# leds.net
KiCad netlist of a schematic drawn in Altium Designer
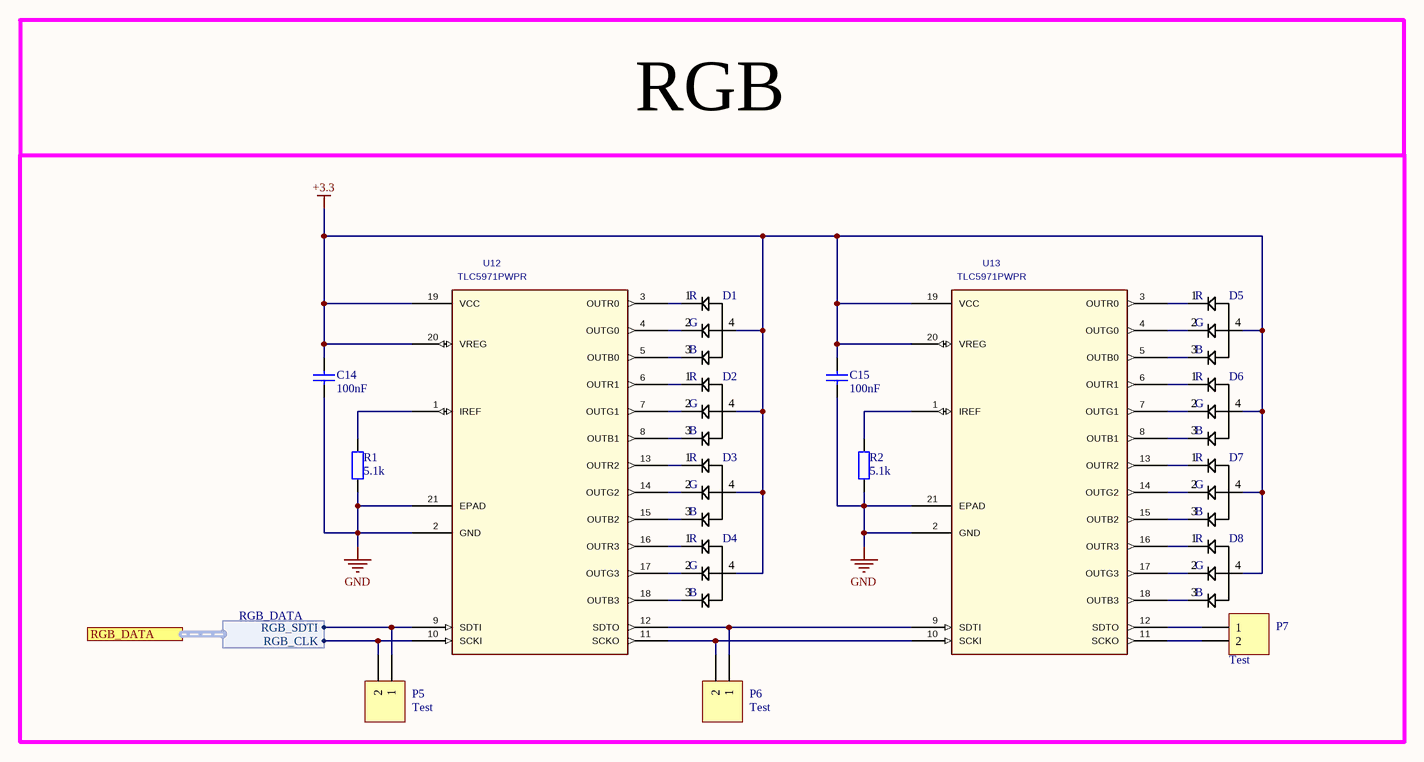
[diagram p0: leds.SchDoc]

(export (version "E")
  (design (tool "Eeschema 10.0.6"))
  (components
    (comp (ref "C14")
      (value "100nF")
      (footprint "CAP_0402i_1005m -N")
      (description "capacitor")
      (libsource (lib "IDSC std generic parts") (part "Cap"))
    )
    (comp (ref "C15")
      (value "100nF")
      (footprint "CAP_0402i_1005m -N")
      (description "capacitor")
      (libsource (lib "IDSC std generic parts") (part "Cap"))
    )
    (comp (ref "D1")
      (value "67-23/R6GHBHC-B01/2T")
      (footprint "*PLCC-4")
      (libsource (lib "BMA_lib") (part "67-23/R6GHBHC-B01/2T"))
    )
    (comp (ref "D2")
      (value "67-23/R6GHBHC-B01/2T")
      (footprint "*PLCC-4")
      (libsource (lib "BMA_lib") (part "67-23/R6GHBHC-B01/2T"))
    )
    (comp (ref "D3")
      (value "67-23/R6GHBHC-B01/2T")
      (footprint "*PLCC-4")
      (libsource (lib "BMA_lib") (part "67-23/R6GHBHC-B01/2T"))
    )
    (comp (ref "D4")
      (value "67-23/R6GHBHC-B01/2T")
      (footprint "*PLCC-4")
      (libsource (lib "BMA_lib") (part "67-23/R6GHBHC-B01/2T"))
    )
    (comp (ref "D5")
      (value "67-23/R6GHBHC-B01/2T")
      (footprint "*PLCC-4")
      (libsource (lib "BMA_lib") (part "67-23/R6GHBHC-B01/2T"))
    )
    (comp (ref "D6")
      (value "67-23/R6GHBHC-B01/2T")
      (footprint "*PLCC-4")
      (libsource (lib "BMA_lib") (part "67-23/R6GHBHC-B01/2T"))
    )
    (comp (ref "D7")
      (value "67-23/R6GHBHC-B01/2T")
      (footprint "*PLCC-4")
      (libsource (lib "BMA_lib") (part "67-23/R6GHBHC-B01/2T"))
    )
    (comp (ref "D8")
      (value "67-23/R6GHBHC-B01/2T")
      (footprint "*PLCC-4")
      (libsource (lib "BMA_lib") (part "67-23/R6GHBHC-B01/2T"))
    )
    (comp (ref "P5")
      (value "Test")
      (footprint "HDR1X2")
      (description "Header, 2-Pin")
      (libsource (lib "") (part "Header 2_1"))
    )
    (comp (ref "P6")
      (value "Test")
      (footprint "HDR1X2")
      (description "Header, 2-Pin")
      (libsource (lib "") (part "Header 2_1"))
    )
    (comp (ref "P7")
      (value "Test")
      (footprint "HDR1X2")
      (description "Header, 2-Pin")
      (libsource (lib "IDSC std connectors") (part "Header 2"))
    )
    (comp (ref "R1")
      (value "5.1k")
      (footprint "RES_0603i_1608m -N")
      (description "Resistor")
      (libsource (lib "IDSC std generic parts") (part "Res"))
    )
    (comp (ref "R2")
      (value "5.1k")
      (footprint "RES_0603i_1608m -N")
      (description "Resistor")
      (libsource (lib "IDSC std generic parts") (part "Res"))
    )
    (comp (ref "U12")
      (value "TLC5971PWPR")
      (footprint "PWP20_3P43X2P701")
      (fields (field (name "MANUFACTURER") "Texas Instruments"))
      (libsource (lib "BMA_lib") (part "TLC5971PWPR"))
    )
    (comp (ref "U13")
      (value "TLC5971PWPR")
      (footprint "PWP20_3P43X2P701")
      (fields (field (name "MANUFACTURER") "Texas Instruments"))
      (libsource (lib "BMA_lib") (part "TLC5971PWPR"))
    )
  )
  (nets
    (net (code "2") (name "+3.3") (class "Default")
      (node (ref "C14") (pin "2") (pinfunction "2_2") (pintype "passive"))
      (node (ref "C15") (pin "2") (pinfunction "2_2") (pintype "passive"))
      (node (ref "D1") (pin "4") (pinfunction "B14_4") (pintype "passive"))
      (node (ref "D2") (pin "4") (pinfunction "B14_4") (pintype "passive"))
      (node (ref "D3") (pin "4") (pinfunction "B14_4") (pintype "passive"))
      (node (ref "D4") (pin "4") (pinfunction "B14_4") (pintype "passive"))
      (node (ref "D5") (pin "4") (pinfunction "B14_4") (pintype "passive"))
      (node (ref "D6") (pin "4") (pinfunction "B14_4") (pintype "passive"))
      (node (ref "D7") (pin "4") (pinfunction "B14_4") (pintype "passive"))
      (node (ref "D8") (pin "4") (pinfunction "B14_4") (pintype "passive"))
      (node (ref "U12") (pin "19") (pinfunction "VCC_19") (pintype "power_in"))
      (node (ref "U12") (pin "20") (pinfunction "VREG_20") (pintype "bidirectional"))
      (node (ref "U13") (pin "19") (pinfunction "VCC_19") (pintype "power_in"))
      (node (ref "U13") (pin "20") (pinfunction "VREG_20") (pintype "bidirectional"))
    )
    (net (code "4") (name "GND") (class "Default")
      (node (ref "C14") (pin "1") (pinfunction "1_1") (pintype "passive"))
      (node (ref "C15") (pin "1") (pinfunction "1_1") (pintype "passive"))
      (node (ref "R1") (pin "1") (pinfunction "1_1") (pintype "passive"))
      (node (ref "R2") (pin "1") (pinfunction "1_1") (pintype "passive"))
      (node (ref "U12") (pin "2") (pinfunction "GND_2") (pintype "power_in"))
      (node (ref "U12") (pin "21") (pinfunction "EPAD_21") (pintype "passive"))
      (node (ref "U13") (pin "2") (pinfunction "GND_2") (pintype "power_in"))
      (node (ref "U13") (pin "21") (pinfunction "EPAD_21") (pintype "passive"))
    )
    (net (code "5") (name "Net-(D1-B15)") (class "Default")
      (node (ref "D1") (pin "1") (pinfunction "B15_1") (pintype "passive"))
      (node (ref "U12") (pin "3") (pinfunction "OUTR0_3") (pintype "output"))
    )
    (net (code "6") (name "Net-(D1-B16)") (class "Default")
      (node (ref "D1") (pin "2") (pinfunction "B16_2") (pintype "passive"))
      (node (ref "U12") (pin "4") (pinfunction "OUTG0_4") (pintype "output"))
    )
    (net (code "7") (name "Net-(D1-B17)") (class "Default")
      (node (ref "D1") (pin "3") (pinfunction "B17_3") (pintype "passive"))
      (node (ref "U12") (pin "5") (pinfunction "OUTB0_5") (pintype "output"))
    )
    (net (code "8") (name "Net-(D2-B15)") (class "Default")
      (node (ref "D2") (pin "1") (pinfunction "B15_1") (pintype "passive"))
      (node (ref "U12") (pin "6") (pinfunction "OUTR1_6") (pintype "output"))
    )
    (net (code "9") (name "Net-(D2-B16)") (class "Default")
      (node (ref "D2") (pin "2") (pinfunction "B16_2") (pintype "passive"))
      (node (ref "U12") (pin "7") (pinfunction "OUTG1_7") (pintype "output"))
    )
    (net (code "10") (name "Net-(D2-B17)") (class "Default")
      (node (ref "D2") (pin "3") (pinfunction "B17_3") (pintype "passive"))
      (node (ref "U12") (pin "8") (pinfunction "OUTB1_8") (pintype "output"))
    )
    (net (code "11") (name "Net-(D3-B15)") (class "Default")
      (node (ref "D3") (pin "1") (pinfunction "B15_1") (pintype "passive"))
      (node (ref "U12") (pin "13") (pinfunction "OUTR2_13") (pintype "output"))
    )
    (net (code "12") (name "Net-(D3-B16)") (class "Default")
      (node (ref "D3") (pin "2") (pinfunction "B16_2") (pintype "passive"))
      (node (ref "U12") (pin "14") (pinfunction "OUTG2_14") (pintype "output"))
    )
    (net (code "13") (name "Net-(D3-B17)") (class "Default")
      (node (ref "D3") (pin "3") (pinfunction "B17_3") (pintype "passive"))
      (node (ref "U12") (pin "15") (pinfunction "OUTB2_15") (pintype "output"))
    )
    (net (code "14") (name "Net-(D4-B15)") (class "Default")
      (node (ref "D4") (pin "1") (pinfunction "B15_1") (pintype "passive"))
      (node (ref "U12") (pin "16") (pinfunction "OUTR3_16") (pintype "output"))
    )
    (net (code "15") (name "Net-(D4-B16)") (class "Default")
      (node (ref "D4") (pin "2") (pinfunction "B16_2") (pintype "passive"))
      (node (ref "U12") (pin "17") (pinfunction "OUTG3_17") (pintype "output"))
    )
    (net (code "16") (name "Net-(D4-B17)") (class "Default")
      (node (ref "D4") (pin "3") (pinfunction "B17_3") (pintype "passive"))
      (node (ref "U12") (pin "18") (pinfunction "OUTB3_18") (pintype "output"))
    )
    (net (code "17") (name "Net-(D5-B15)") (class "Default")
      (node (ref "D5") (pin "1") (pinfunction "B15_1") (pintype "passive"))
      (node (ref "U13") (pin "3") (pinfunction "OUTR0_3") (pintype "output"))
    )
    (net (code "18") (name "Net-(D5-B16)") (class "Default")
      (node (ref "D5") (pin "2") (pinfunction "B16_2") (pintype "passive"))
      (node (ref "U13") (pin "4") (pinfunction "OUTG0_4") (pintype "output"))
    )
    (net (code "19") (name "Net-(D5-B17)") (class "Default")
      (node (ref "D5") (pin "3") (pinfunction "B17_3") (pintype "passive"))
      (node (ref "U13") (pin "5") (pinfunction "OUTB0_5") (pintype "output"))
    )
    (net (code "20") (name "Net-(D6-B15)") (class "Default")
      (node (ref "D6") (pin "1") (pinfunction "B15_1") (pintype "passive"))
      (node (ref "U13") (pin "6") (pinfunction "OUTR1_6") (pintype "output"))
    )
    (net (code "21") (name "Net-(D6-B16)") (class "Default")
      (node (ref "D6") (pin "2") (pinfunction "B16_2") (pintype "passive"))
      (node (ref "U13") (pin "7") (pinfunction "OUTG1_7") (pintype "output"))
    )
    (net (code "22") (name "Net-(D6-B17)") (class "Default")
      (node (ref "D6") (pin "3") (pinfunction "B17_3") (pintype "passive"))
      (node (ref "U13") (pin "8") (pinfunction "OUTB1_8") (pintype "output"))
    )
    (net (code "23") (name "Net-(D7-B15)") (class "Default")
      (node (ref "D7") (pin "1") (pinfunction "B15_1") (pintype "passive"))
      (node (ref "U13") (pin "13") (pinfunction "OUTR2_13") (pintype "output"))
    )
    (net (code "24") (name "Net-(D7-B16)") (class "Default")
      (node (ref "D7") (pin "2") (pinfunction "B16_2") (pintype "passive"))
      (node (ref "U13") (pin "14") (pinfunction "OUTG2_14") (pintype "output"))
    )
    (net (code "25") (name "Net-(D7-B17)") (class "Default")
      (node (ref "D7") (pin "3") (pinfunction "B17_3") (pintype "passive"))
      (node (ref "U13") (pin "15") (pinfunction "OUTB2_15") (pintype "output"))
    )
    (net (code "26") (name "Net-(D8-B15)") (class "Default")
      (node (ref "D8") (pin "1") (pinfunction "B15_1") (pintype "passive"))
      (node (ref "U13") (pin "16") (pinfunction "OUTR3_16") (pintype "output"))
    )
    (net (code "27") (name "Net-(D8-B16)") (class "Default")
      (node (ref "D8") (pin "2") (pinfunction "B16_2") (pintype "passive"))
      (node (ref "U13") (pin "17") (pinfunction "OUTG3_17") (pintype "output"))
    )
    (net (code "28") (name "Net-(D8-B17)") (class "Default")
      (node (ref "D8") (pin "3") (pinfunction "B17_3") (pintype "passive"))
      (node (ref "U13") (pin "18") (pinfunction "OUTB3_18") (pintype "output"))
    )
    (net (code "29") (name "Net-(U12-IREF)") (class "Default")
      (node (ref "R1") (pin "2") (pinfunction "2_2") (pintype "passive"))
      (node (ref "U12") (pin "1") (pinfunction "IREF_1") (pintype "bidirectional"))
    )
    (net (code "30") (name "Net-(U12-SCKI)") (class "Default")
      (node (ref "P5") (pin "2") (pinfunction "2_2") (pintype "passive"))
      (node (ref "U12") (pin "10") (pinfunction "SCKI_10") (pintype "input"))
    )
    (net (code "31") (name "Net-(U12-SCKO)") (class "Default")
      (node (ref "P6") (pin "2") (pinfunction "2_2") (pintype "passive"))
      (node (ref "U12") (pin "11") (pinfunction "SCKO_11") (pintype "output"))
      (node (ref "U13") (pin "10") (pinfunction "SCKI_10") (pintype "input"))
    )
    (net (code "32") (name "Net-(U12-SDTI)") (class "Default")
      (node (ref "P5") (pin "1") (pinfunction "1_1") (pintype "passive"))
      (node (ref "U12") (pin "9") (pinfunction "SDTI_9") (pintype "input"))
    )
    (net (code "33") (name "Net-(U12-SDTO)") (class "Default")
      (node (ref "P6") (pin "1") (pinfunction "1_1") (pintype "passive"))
      (node (ref "U12") (pin "12") (pinfunction "SDTO_12") (pintype "output"))
      (node (ref "U13") (pin "9") (pinfunction "SDTI_9") (pintype "input"))
    )
    (net (code "34") (name "Net-(U13-IREF)") (class "Default")
      (node (ref "R2") (pin "2") (pinfunction "2_2") (pintype "passive"))
      (node (ref "U13") (pin "1") (pinfunction "IREF_1") (pintype "bidirectional"))
    )
    (net (code "35") (name "Net-(U13-SCKO)") (class "Default")
      (node (ref "P7") (pin "2") (pinfunction "2_2") (pintype "passive"))
      (node (ref "U13") (pin "11") (pinfunction "SCKO_11") (pintype "output"))
    )
    (net (code "36") (name "Net-(U13-SDTO)") (class "Default")
      (node (ref "P7") (pin "1") (pinfunction "1_1") (pintype "passive"))
      (node (ref "U13") (pin "12") (pinfunction "SDTO_12") (pintype "output"))
    )
  )
)
